# AD9363_Power_Misc.net
KiCad netlist of a schematic drawn in Altium Designer
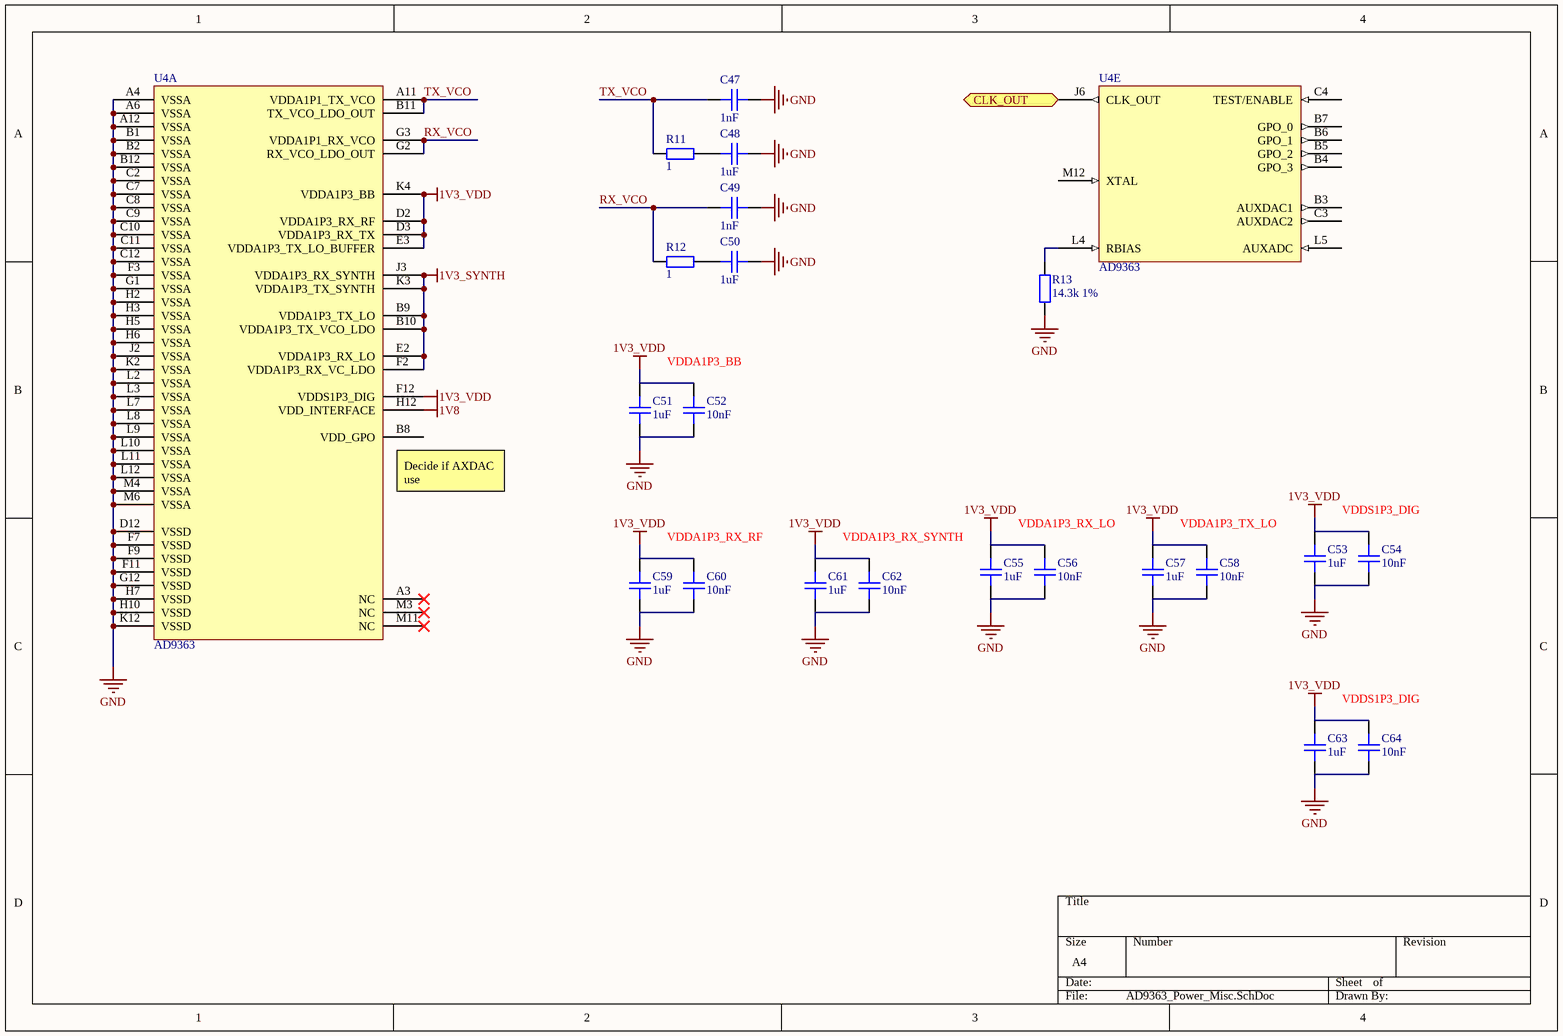
[diagram p0: AD9363_Power_Misc.SchDoc]

(export (version "E")
  (design (tool "Eeschema 10.0.6"))
  (components
    (comp (ref "C47") (value "1nF") (footprint "CAP0402") (libsource (lib "WaveRadio") (part "Cap_0402")))
    (comp (ref "C48") (value "1uF") (footprint "CAP0402") (libsource (lib "WaveRadio") (part "Cap_0402")))
    (comp (ref "C49") (value "1nF") (footprint "CAP0402") (libsource (lib "WaveRadio") (part "Cap_0402")))
    (comp (ref "C50") (value "1uF") (footprint "CAP0402") (libsource (lib "WaveRadio") (part "Cap_0402")))
    (comp (ref "C51") (value "1uF") (footprint "CAP0402") (libsource (lib "WaveRadio") (part "Cap_0402")))
    (comp (ref "C52") (value "10nF") (footprint "CAP0402") (libsource (lib "WaveRadio") (part "Cap_0402")))
    (comp (ref "C53") (value "1uF") (footprint "CAP0402") (libsource (lib "WaveRadio") (part "Cap_0402")))
    (comp (ref "C54") (value "10nF") (footprint "CAP0402") (libsource (lib "WaveRadio") (part "Cap_0402")))
    (comp (ref "C55") (value "1uF") (footprint "CAP0402") (libsource (lib "WaveRadio") (part "Cap_0402")))
    (comp (ref "C56") (value "10nF") (footprint "CAP0402") (libsource (lib "WaveRadio") (part "Cap_0402")))
    (comp (ref "C57") (value "1uF") (footprint "CAP0402") (libsource (lib "WaveRadio") (part "Cap_0402")))
    (comp (ref "C58") (value "10nF") (footprint "CAP0402") (libsource (lib "WaveRadio") (part "Cap_0402")))
    (comp (ref "C59") (value "1uF") (footprint "CAP0402") (libsource (lib "WaveRadio") (part "Cap_0402")))
    (comp (ref "C60") (value "10nF") (footprint "CAP0402") (libsource (lib "WaveRadio") (part "Cap_0402")))
    (comp (ref "C61") (value "1uF") (footprint "CAP0402") (libsource (lib "WaveRadio") (part "Cap_0402")))
    (comp (ref "C62") (value "10nF") (footprint "CAP0402") (libsource (lib "WaveRadio") (part "Cap_0402")))
    (comp (ref "C63") (value "1uF") (footprint "CAP0402") (libsource (lib "WaveRadio") (part "Cap_0402")))
    (comp (ref "C64") (value "10nF") (footprint "CAP0402") (libsource (lib "WaveRadio") (part "Cap_0402")))
    (comp (ref "R11") (value "1") (footprint "RES0402") (libsource (lib "WaveRadio") (part "Res_0402")))
    (comp (ref "R12") (value "1") (footprint "RES0402") (libsource (lib "WaveRadio") (part "Res_0402")))
    (comp (ref "R13")
      (value "14.3k 1%")
      (footprint "RES0402")
      (libsource (lib "WaveRadio") (part "Res_0402"))
    )
    (comp (ref "U4")
      (value "AD9363")
      (footprint "BGA144C80P12X12_1000X1000X100")
      (libsource (lib "WaveRadio") (part "AD9363"))
    )
  )
  (nets
    (net (code "1") (name "/CLK_OUT") (class "Default")
      (node (ref "U4") (pin "J6") (pinfunction "CLK_OUT_J6") (pintype "output"))
    )
    (net (code "2") (name "/RX_VCO") (class "Default")
      (node (ref "U4") (pin "G2") (pinfunction "RX_VCO_LDO_OUT_G2") (pintype "power_in"))
      (node (ref "U4") (pin "G3") (pinfunction "VDDA1P1_RX_VCO_G3") (pintype "power_in"))
    )
    (net (code "3") (name "/TX_VCO") (class "Default")
      (node (ref "U4") (pin "A11") (pinfunction "VDDA1P1_TX_VCO_A11") (pintype "power_in"))
      (node (ref "U4") (pin "B11") (pinfunction "TX_VCO_LDO_OUT_B11") (pintype "power_in"))
    )
    (net (code "4") (name "1V3_SYNTH") (class "Default")
      (node (ref "U4") (pin "B10") (pinfunction "VDDA1P3_TX_VCO_LDO_B10") (pintype "power_in"))
      (node (ref "U4") (pin "B9") (pinfunction "VDDA1P3_TX_LO_B9") (pintype "power_in"))
      (node (ref "U4") (pin "E2") (pinfunction "VDDA1P3_RX_LO_E2") (pintype "power_in"))
      (node (ref "U4") (pin "F2") (pinfunction "VDDA1P3_RX_VC_LDO_F2") (pintype "power_in"))
      (node (ref "U4") (pin "J3") (pinfunction "VDDA1P3_RX_SYNTH_J3") (pintype "power_in"))
      (node (ref "U4") (pin "K3") (pinfunction "VDDA1P3_TX_SYNTH_K3") (pintype "power_in"))
    )
    (net (code "5") (name "1V3_VDD") (class "Default")
      (node (ref "U4") (pin "D2") (pinfunction "VDDA1P3_RX_RF_D2") (pintype "power_in"))
      (node (ref "U4") (pin "D3") (pinfunction "VDDA1P3_RX_TX_D3") (pintype "power_in"))
      (node (ref "U4") (pin "E3") (pinfunction "VDDA1P3_TX_LO_BUFFER_E3") (pintype "power_in"))
      (node (ref "U4") (pin "F12") (pinfunction "VDDS1P3_DIG_F12") (pintype "power_in"))
      (node (ref "U4") (pin "K4") (pinfunction "VDDA1P3_BB_K4") (pintype "power_in"))
    )
    (net (code "6") (name "1V8") (class "Default")
      (node (ref "U4") (pin "H12") (pinfunction "VDD_INTERFACE_H12") (pintype "power_in"))
    )
    (net (code "7") (name "GND") (class "Default")
      (node (ref "U4") (pin "A12") (pinfunction "VSSA_A12") (pintype "power_in"))
      (node (ref "U4") (pin "A4") (pinfunction "VSSA_A4") (pintype "power_in"))
      (node (ref "U4") (pin "A6") (pinfunction "VSSA_A6") (pintype "power_in"))
      (node (ref "U4") (pin "B1") (pinfunction "VSSA_B1") (pintype "power_in"))
      (node (ref "U4") (pin "B12") (pinfunction "VSSA_B12") (pintype "power_in"))
      (node (ref "U4") (pin "B2") (pinfunction "VSSA_B2") (pintype "power_in"))
      (node (ref "U4") (pin "C10") (pinfunction "VSSA_C10") (pintype "power_in"))
      (node (ref "U4") (pin "C11") (pinfunction "VSSA_C11") (pintype "power_in"))
      (node (ref "U4") (pin "C12") (pinfunction "VSSA_C12") (pintype "power_in"))
      (node (ref "U4") (pin "C2") (pinfunction "VSSA_C2") (pintype "power_in"))
      (node (ref "U4") (pin "C7") (pinfunction "VSSA_C7") (pintype "power_in"))
      (node (ref "U4") (pin "C8") (pinfunction "VSSA_C8") (pintype "power_in"))
      (node (ref "U4") (pin "C9") (pinfunction "VSSA_C9") (pintype "power_in"))
      (node (ref "U4") (pin "D12") (pinfunction "VSSD_D12") (pintype "power_in"))
      (node (ref "U4") (pin "F11") (pinfunction "VSSD_F11") (pintype "power_in"))
      (node (ref "U4") (pin "F3") (pinfunction "VSSA_F3") (pintype "power_in"))
      (node (ref "U4") (pin "F7") (pinfunction "VSSD_F7") (pintype "power_in"))
      (node (ref "U4") (pin "F9") (pinfunction "VSSD_F9") (pintype "power_in"))
      (node (ref "U4") (pin "G1") (pinfunction "VSSA_G1") (pintype "power_in"))
      (node (ref "U4") (pin "G12") (pinfunction "VSSD_G12") (pintype "power_in"))
      (node (ref "U4") (pin "H10") (pinfunction "VSSD_H10") (pintype "power_in"))
      (node (ref "U4") (pin "H2") (pinfunction "VSSA_H2") (pintype "power_in"))
      (node (ref "U4") (pin "H3") (pinfunction "VSSA_H3") (pintype "power_in"))
      (node (ref "U4") (pin "H5") (pinfunction "VSSA_H5") (pintype "power_in"))
      (node (ref "U4") (pin "H6") (pinfunction "VSSA_H6") (pintype "power_in"))
      (node (ref "U4") (pin "H7") (pinfunction "VSSD_H7") (pintype "power_in"))
      (node (ref "U4") (pin "J2") (pinfunction "VSSA_J2") (pintype "power_in"))
      (node (ref "U4") (pin "K12") (pinfunction "VSSD_K12") (pintype "power_in"))
      (node (ref "U4") (pin "K2") (pinfunction "VSSA_K2") (pintype "power_in"))
      (node (ref "U4") (pin "L10") (pinfunction "VSSA_L10") (pintype "power_in"))
      (node (ref "U4") (pin "L11") (pinfunction "VSSA_L11") (pintype "power_in"))
      (node (ref "U4") (pin "L12") (pinfunction "VSSA_L12") (pintype "power_in"))
      (node (ref "U4") (pin "L2") (pinfunction "VSSA_L2") (pintype "power_in"))
      (node (ref "U4") (pin "L3") (pinfunction "VSSA_L3") (pintype "power_in"))
      (node (ref "U4") (pin "L7") (pinfunction "VSSA_L7") (pintype "power_in"))
      (node (ref "U4") (pin "L8") (pinfunction "VSSA_L8") (pintype "power_in"))
      (node (ref "U4") (pin "L9") (pinfunction "VSSA_L9") (pintype "power_in"))
      (node (ref "U4") (pin "M4") (pinfunction "VSSA_M4") (pintype "power_in"))
      (node (ref "U4") (pin "M6") (pinfunction "VSSA_M6") (pintype "power_in"))
    )
    (net (code "8") (name "unconnected-(C47-Pad1)") (class "Default")
      (node (ref "C47") (pin "1") (pinfunction "1_1") (pintype "passive"))
    )
    (net (code "9") (name "unconnected-(C47-Pad2)") (class "Default")
      (node (ref "C47") (pin "2") (pinfunction "2_2") (pintype "passive"))
    )
    (net (code "10") (name "unconnected-(C48-Pad1)") (class "Default")
      (node (ref "C48") (pin "1") (pinfunction "1_1") (pintype "passive"))
    )
    (net (code "11") (name "unconnected-(C48-Pad2)") (class "Default")
      (node (ref "C48") (pin "2") (pinfunction "2_2") (pintype "passive"))
    )
    (net (code "12") (name "unconnected-(C49-Pad1)") (class "Default")
      (node (ref "C49") (pin "1") (pinfunction "1_1") (pintype "passive"))
    )
    (net (code "13") (name "unconnected-(C49-Pad2)") (class "Default")
      (node (ref "C49") (pin "2") (pinfunction "2_2") (pintype "passive"))
    )
    (net (code "14") (name "unconnected-(C50-Pad1)") (class "Default")
      (node (ref "C50") (pin "1") (pinfunction "1_1") (pintype "passive"))
    )
    (net (code "15") (name "unconnected-(C50-Pad2)") (class "Default")
      (node (ref "C50") (pin "2") (pinfunction "2_2") (pintype "passive"))
    )
    (net (code "16") (name "unconnected-(C51-Pad1)") (class "Default")
      (node (ref "C51") (pin "1") (pinfunction "1_1") (pintype "passive"))
    )
    (net (code "17") (name "unconnected-(C51-Pad2)") (class "Default")
      (node (ref "C51") (pin "2") (pinfunction "2_2") (pintype "passive"))
    )
    (net (code "18") (name "unconnected-(C52-Pad1)") (class "Default")
      (node (ref "C52") (pin "1") (pinfunction "1_1") (pintype "passive"))
    )
    (net (code "19") (name "unconnected-(C52-Pad2)") (class "Default")
      (node (ref "C52") (pin "2") (pinfunction "2_2") (pintype "passive"))
    )
    (net (code "20") (name "unconnected-(C53-Pad1)") (class "Default")
      (node (ref "C53") (pin "1") (pinfunction "1_1") (pintype "passive"))
    )
    (net (code "21") (name "unconnected-(C53-Pad2)") (class "Default")
      (node (ref "C53") (pin "2") (pinfunction "2_2") (pintype "passive"))
    )
    (net (code "22") (name "unconnected-(C54-Pad1)") (class "Default")
      (node (ref "C54") (pin "1") (pinfunction "1_1") (pintype "passive"))
    )
    (net (code "23") (name "unconnected-(C54-Pad2)") (class "Default")
      (node (ref "C54") (pin "2") (pinfunction "2_2") (pintype "passive"))
    )
    (net (code "24") (name "unconnected-(C55-Pad1)") (class "Default")
      (node (ref "C55") (pin "1") (pinfunction "1_1") (pintype "passive"))
    )
    (net (code "25") (name "unconnected-(C55-Pad2)") (class "Default")
      (node (ref "C55") (pin "2") (pinfunction "2_2") (pintype "passive"))
    )
    (net (code "26") (name "unconnected-(C56-Pad1)") (class "Default")
      (node (ref "C56") (pin "1") (pinfunction "1_1") (pintype "passive"))
    )
    (net (code "27") (name "unconnected-(C56-Pad2)") (class "Default")
      (node (ref "C56") (pin "2") (pinfunction "2_2") (pintype "passive"))
    )
    (net (code "28") (name "unconnected-(C57-Pad1)") (class "Default")
      (node (ref "C57") (pin "1") (pinfunction "1_1") (pintype "passive"))
    )
    (net (code "29") (name "unconnected-(C57-Pad2)") (class "Default")
      (node (ref "C57") (pin "2") (pinfunction "2_2") (pintype "passive"))
    )
    (net (code "30") (name "unconnected-(C58-Pad1)") (class "Default")
      (node (ref "C58") (pin "1") (pinfunction "1_1") (pintype "passive"))
    )
    (net (code "31") (name "unconnected-(C58-Pad2)") (class "Default")
      (node (ref "C58") (pin "2") (pinfunction "2_2") (pintype "passive"))
    )
    (net (code "32") (name "unconnected-(C59-Pad1)") (class "Default")
      (node (ref "C59") (pin "1") (pinfunction "1_1") (pintype "passive"))
    )
    (net (code "33") (name "unconnected-(C59-Pad2)") (class "Default")
      (node (ref "C59") (pin "2") (pinfunction "2_2") (pintype "passive"))
    )
    (net (code "34") (name "unconnected-(C60-Pad1)") (class "Default")
      (node (ref "C60") (pin "1") (pinfunction "1_1") (pintype "passive"))
    )
    (net (code "35") (name "unconnected-(C60-Pad2)") (class "Default")
      (node (ref "C60") (pin "2") (pinfunction "2_2") (pintype "passive"))
    )
    (net (code "36") (name "unconnected-(C61-Pad1)") (class "Default")
      (node (ref "C61") (pin "1") (pinfunction "1_1") (pintype "passive"))
    )
    (net (code "37") (name "unconnected-(C61-Pad2)") (class "Default")
      (node (ref "C61") (pin "2") (pinfunction "2_2") (pintype "passive"))
    )
    (net (code "38") (name "unconnected-(C62-Pad1)") (class "Default")
      (node (ref "C62") (pin "1") (pinfunction "1_1") (pintype "passive"))
    )
    (net (code "39") (name "unconnected-(C62-Pad2)") (class "Default")
      (node (ref "C62") (pin "2") (pinfunction "2_2") (pintype "passive"))
    )
    (net (code "40") (name "unconnected-(C63-Pad1)") (class "Default")
      (node (ref "C63") (pin "1") (pinfunction "1_1") (pintype "passive"))
    )
    (net (code "41") (name "unconnected-(C63-Pad2)") (class "Default")
      (node (ref "C63") (pin "2") (pinfunction "2_2") (pintype "passive"))
    )
    (net (code "42") (name "unconnected-(C64-Pad1)") (class "Default")
      (node (ref "C64") (pin "1") (pinfunction "1_1") (pintype "passive"))
    )
    (net (code "43") (name "unconnected-(C64-Pad2)") (class "Default")
      (node (ref "C64") (pin "2") (pinfunction "2_2") (pintype "passive"))
    )
    (net (code "44") (name "unconnected-(R11-Pad1)") (class "Default")
      (node (ref "R11") (pin "1") (pintype "passive"))
    )
    (net (code "45") (name "unconnected-(R11-Pad2)") (class "Default")
      (node (ref "R11") (pin "2") (pintype "passive"))
    )
    (net (code "46") (name "unconnected-(R12-Pad1)") (class "Default")
      (node (ref "R12") (pin "1") (pintype "passive"))
    )
    (net (code "47") (name "unconnected-(R12-Pad2)") (class "Default")
      (node (ref "R12") (pin "2") (pintype "passive"))
    )
    (net (code "48") (name "unconnected-(R13-Pad1)") (class "Default")
      (node (ref "R13") (pin "1") (pintype "passive"))
    )
    (net (code "49") (name "unconnected-(R13-Pad2)") (class "Default")
      (node (ref "R13") (pin "2") (pintype "passive"))
    )
    (net (code "50") (name "unconnected-(U4A-NC-PadA3)") (class "Default")
      (node (ref "U4") (pin "A3") (pinfunction "NC_A3") (pintype "power_in+no_connect"))
    )
    (net (code "51") (name "unconnected-(U4A-NC-PadM3)") (class "Default")
      (node (ref "U4") (pin "M3") (pinfunction "NC_M3") (pintype "power_in+no_connect"))
    )
    (net (code "52") (name "unconnected-(U4A-NC-PadM11)") (class "Default")
      (node (ref "U4") (pin "M11") (pinfunction "NC_M11") (pintype "power_in+no_connect"))
    )
    (net (code "53") (name "unconnected-(U4A-VDD_GPO-PadB8)") (class "Default")
      (node (ref "U4") (pin "B8") (pinfunction "VDD_GPO_B8") (pintype "power_in"))
    )
    (net (code "54") (name "unconnected-(U4E-AUXADC-PadL5)") (class "Default")
      (node (ref "U4") (pin "L5") (pinfunction "AUXADC_L5") (pintype "input"))
    )
    (net (code "55") (name "unconnected-(U4E-AUXDAC1-PadB3)") (class "Default")
      (node (ref "U4") (pin "B3") (pinfunction "AUXDAC1_B3") (pintype "output"))
    )
    (net (code "56") (name "unconnected-(U4E-AUXDAC2-PadC3)") (class "Default")
      (node (ref "U4") (pin "C3") (pinfunction "AUXDAC2_C3") (pintype "output"))
    )
    (net (code "57") (name "unconnected-(U4E-GPO_0-PadB7)") (class "Default")
      (node (ref "U4") (pin "B7") (pinfunction "GPO_0_B7") (pintype "output"))
    )
    (net (code "58") (name "unconnected-(U4E-GPO_1-PadB6)") (class "Default")
      (node (ref "U4") (pin "B6") (pinfunction "GPO_1_B6") (pintype "output"))
    )
    (net (code "59") (name "unconnected-(U4E-GPO_2-PadB5)") (class "Default")
      (node (ref "U4") (pin "B5") (pinfunction "GPO_2_B5") (pintype "output"))
    )
    (net (code "60") (name "unconnected-(U4E-GPO_3-PadB4)") (class "Default")
      (node (ref "U4") (pin "B4") (pinfunction "GPO_3_B4") (pintype "output"))
    )
    (net (code "61") (name "unconnected-(U4E-RBIAS-PadL4)") (class "Default")
      (node (ref "U4") (pin "L4") (pinfunction "RBIAS_L4") (pintype "input"))
    )
    (net (code "62") (name "unconnected-(U4E-TEST{slash}ENABLE-PadC4)") (class "Default")
      (node (ref "U4") (pin "C4") (pinfunction "TEST/ENABLE_C4") (pintype "input"))
    )
    (net (code "63") (name "unconnected-(U4E-XTAL-PadM12)") (class "Default")
      (node (ref "U4") (pin "M12") (pinfunction "XTAL_M12") (pintype "input"))
    )
  )
)
